# Fuel_Gauge_v1_0.net
KiCad netlist of a schematic drawn in EAGLE
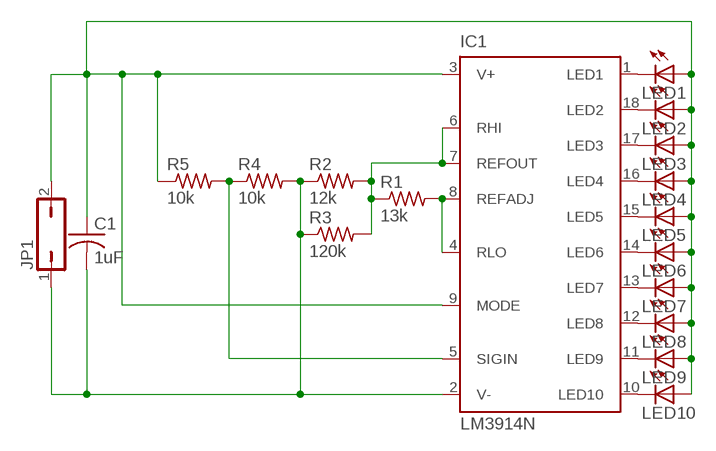
[diagram p0: schematic, sheet 1]

(export (version "E")
  (design (tool "Eeschema 10.0.6"))
  (components
    (comp (ref "C1")
      (value "1uF")
      (footprint "eagle-import:C0603")
      (libsource (lib "eagle-import") (part "C-USC0603"))
    )
    (comp (ref "IC1")
      (value "LM3914N")
      (footprint "eagle-import:DIL18")
      (libsource (lib "eagle-import") (part "LM391N4"))
    )
    (comp (ref "JP1")
      (value "JP1Q")
      (footprint "eagle-import:JP1")
      (libsource (lib "eagle-import") (part "JP1Q"))
    )
    (comp (ref "LED1")
      (value "LEDCHIPLED_0603")
      (footprint "eagle-import:CHIPLED_0603")
      (libsource (lib "eagle-import") (part "LEDCHIPLED_0603"))
    )
    (comp (ref "LED2")
      (value "LEDCHIPLED_0603")
      (footprint "eagle-import:CHIPLED_0603")
      (libsource (lib "eagle-import") (part "LEDCHIPLED_0603"))
    )
    (comp (ref "LED3")
      (value "LEDCHIPLED_0603")
      (footprint "eagle-import:CHIPLED_0603")
      (libsource (lib "eagle-import") (part "LEDCHIPLED_0603"))
    )
    (comp (ref "LED4")
      (value "LEDCHIPLED_0603")
      (footprint "eagle-import:CHIPLED_0603")
      (libsource (lib "eagle-import") (part "LEDCHIPLED_0603"))
    )
    (comp (ref "LED5")
      (value "LEDCHIPLED_0603")
      (footprint "eagle-import:CHIPLED_0603")
      (libsource (lib "eagle-import") (part "LEDCHIPLED_0603"))
    )
    (comp (ref "LED6")
      (value "LEDCHIPLED_0603")
      (footprint "eagle-import:CHIPLED_0603")
      (libsource (lib "eagle-import") (part "LEDCHIPLED_0603"))
    )
    (comp (ref "LED7")
      (value "LEDCHIPLED_0603")
      (footprint "eagle-import:CHIPLED_0603")
      (libsource (lib "eagle-import") (part "LEDCHIPLED_0603"))
    )
    (comp (ref "LED8")
      (value "LEDCHIPLED_0603")
      (footprint "eagle-import:CHIPLED_0603")
      (libsource (lib "eagle-import") (part "LEDCHIPLED_0603"))
    )
    (comp (ref "LED9")
      (value "LEDCHIPLED_0603")
      (footprint "eagle-import:CHIPLED_0603")
      (libsource (lib "eagle-import") (part "LEDCHIPLED_0603"))
    )
    (comp (ref "LED10")
      (value "LEDCHIPLED_0603")
      (footprint "eagle-import:CHIPLED_0603")
      (libsource (lib "eagle-import") (part "LEDCHIPLED_0603"))
    )
    (comp (ref "R1")
      (value "13k")
      (footprint "eagle-import:R0603")
      (libsource (lib "eagle-import") (part "R-US_R0603"))
    )
    (comp (ref "R2")
      (value "12k")
      (footprint "eagle-import:R0603")
      (libsource (lib "eagle-import") (part "R-US_R0603"))
    )
    (comp (ref "R3")
      (value "120k")
      (footprint "eagle-import:R0603")
      (libsource (lib "eagle-import") (part "R-US_R0603"))
    )
    (comp (ref "R4")
      (value "10k")
      (footprint "eagle-import:R0603")
      (libsource (lib "eagle-import") (part "R-US_R0603"))
    )
    (comp (ref "R5")
      (value "10k")
      (footprint "eagle-import:R0603")
      (libsource (lib "eagle-import") (part "R-US_R0603"))
    )
  )
  (nets
    (net (code "1") (name "Net-(IC1-LED1)") (class "Default")
      (node (ref "IC1") (pin "1") (pinfunction "LED1_1") (pintype "output"))
      (node (ref "LED1") (pin "C") (pinfunction "C_C") (pintype "passive"))
    )
    (net (code "2") (name "Net-(IC1-LED2)") (class "Default")
      (node (ref "IC1") (pin "18") (pinfunction "LED2_18") (pintype "output"))
      (node (ref "LED2") (pin "C") (pinfunction "C_C") (pintype "passive"))
    )
    (net (code "3") (name "Net-(IC1-LED3)") (class "Default")
      (node (ref "IC1") (pin "17") (pinfunction "LED3_17") (pintype "output"))
      (node (ref "LED3") (pin "C") (pinfunction "C_C") (pintype "passive"))
    )
    (net (code "4") (name "Net-(IC1-LED4)") (class "Default")
      (node (ref "IC1") (pin "16") (pinfunction "LED4_16") (pintype "output"))
      (node (ref "LED4") (pin "C") (pinfunction "C_C") (pintype "passive"))
    )
    (net (code "5") (name "Net-(IC1-LED5)") (class "Default")
      (node (ref "IC1") (pin "15") (pinfunction "LED5_15") (pintype "output"))
      (node (ref "LED5") (pin "C") (pinfunction "C_C") (pintype "passive"))
    )
    (net (code "6") (name "Net-(IC1-LED6)") (class "Default")
      (node (ref "IC1") (pin "14") (pinfunction "LED6_14") (pintype "output"))
      (node (ref "LED6") (pin "C") (pinfunction "C_C") (pintype "passive"))
    )
    (net (code "7") (name "Net-(IC1-LED7)") (class "Default")
      (node (ref "IC1") (pin "13") (pinfunction "LED7_13") (pintype "output"))
      (node (ref "LED7") (pin "C") (pinfunction "C_C") (pintype "passive"))
    )
    (net (code "8") (name "Net-(IC1-LED8)") (class "Default")
      (node (ref "IC1") (pin "12") (pinfunction "LED8_12") (pintype "output"))
      (node (ref "LED8") (pin "C") (pinfunction "C_C") (pintype "passive"))
    )
    (net (code "9") (name "Net-(IC1-LED9)") (class "Default")
      (node (ref "IC1") (pin "11") (pinfunction "LED9_11") (pintype "output"))
      (node (ref "LED9") (pin "C") (pinfunction "C_C") (pintype "passive"))
    )
    (net (code "10") (name "Net-(IC1-LED10)") (class "Default")
      (node (ref "IC1") (pin "10") (pinfunction "LED10_10") (pintype "output"))
      (node (ref "LED10") (pin "C") (pinfunction "C_C") (pintype "passive"))
    )
    (net (code "11") (name "Net-(IC1-MODE)") (class "Default")
      (node (ref "C1") (pin "1") (pinfunction "1_1") (pintype "passive"))
      (node (ref "IC1") (pin "3") (pinfunction "V+_3") (pintype "power_in"))
      (node (ref "IC1") (pin "9") (pinfunction "MODE_9") (pintype "input"))
      (node (ref "JP1") (pin "2") (pinfunction "2_2") (pintype "passive"))
      (node (ref "LED1") (pin "A") (pinfunction "A_A") (pintype "passive"))
      (node (ref "LED10") (pin "A") (pinfunction "A_A") (pintype "passive"))
      (node (ref "LED2") (pin "A") (pinfunction "A_A") (pintype "passive"))
      (node (ref "LED3") (pin "A") (pinfunction "A_A") (pintype "passive"))
      (node (ref "LED4") (pin "A") (pinfunction "A_A") (pintype "passive"))
      (node (ref "LED5") (pin "A") (pinfunction "A_A") (pintype "passive"))
      (node (ref "LED6") (pin "A") (pinfunction "A_A") (pintype "passive"))
      (node (ref "LED7") (pin "A") (pinfunction "A_A") (pintype "passive"))
      (node (ref "LED8") (pin "A") (pinfunction "A_A") (pintype "passive"))
      (node (ref "LED9") (pin "A") (pinfunction "A_A") (pintype "passive"))
      (node (ref "R5") (pin "1") (pinfunction "1_1") (pintype "passive"))
    )
    (net (code "12") (name "Net-(IC1-REFADJ)") (class "Default")
      (node (ref "IC1") (pin "4") (pinfunction "RLO_4") (pintype "input"))
      (node (ref "IC1") (pin "8") (pinfunction "REFADJ_8") (pintype "passive"))
      (node (ref "R1") (pin "2") (pinfunction "2_2") (pintype "passive"))
    )
    (net (code "13") (name "Net-(IC1-REFOUT)") (class "Default")
      (node (ref "IC1") (pin "6") (pinfunction "RHI_6") (pintype "input"))
      (node (ref "IC1") (pin "7") (pinfunction "REFOUT_7") (pintype "output"))
      (node (ref "R1") (pin "1") (pinfunction "1_1") (pintype "passive"))
      (node (ref "R2") (pin "2") (pinfunction "2_2") (pintype "passive"))
      (node (ref "R3") (pin "2") (pinfunction "2_2") (pintype "passive"))
    )
    (net (code "14") (name "Net-(IC1-SIGIN)") (class "Default")
      (node (ref "IC1") (pin "5") (pinfunction "SIGIN_5") (pintype "input"))
      (node (ref "R4") (pin "1") (pinfunction "1_1") (pintype "passive"))
      (node (ref "R5") (pin "2") (pinfunction "2_2") (pintype "passive"))
    )
    (net (code "15") (name "Net-(IC1-V-)") (class "Default")
      (node (ref "C1") (pin "2") (pinfunction "2_2") (pintype "passive"))
      (node (ref "IC1") (pin "2") (pinfunction "V-_2") (pintype "power_in"))
      (node (ref "JP1") (pin "1") (pinfunction "1_1") (pintype "passive"))
      (node (ref "R2") (pin "1") (pinfunction "1_1") (pintype "passive"))
      (node (ref "R3") (pin "1") (pinfunction "1_1") (pintype "passive"))
      (node (ref "R4") (pin "2") (pinfunction "2_2") (pintype "passive"))
    )
  )
)
